# PM3_Bosclone_Shield.net
KiCad netlist of a schematic drawn in Altium Designer
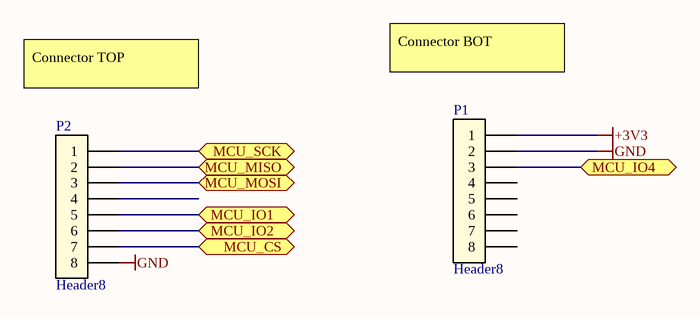
[diagram p0: PM3_Bosclone_Shield.SchDoc]

(export (version "E")
  (design (tool "Eeschema 10.0.6"))
  (components
    (comp (ref "P1")
      (value "Header8")
      (footprint "HEADER_8_40_100THRU SIP")
      (description "Header 8 pin")
      (libsource (lib "mConnector") (part "Header8"))
    )
    (comp (ref "P2")
      (value "Header8")
      (footprint "HEADER_8_40_100THRU SIP")
      (description "Header 8 pin")
      (libsource (lib "mConnector") (part "Header8"))
    )
  )
  (nets
    (net (code "1") (name "+3V3") (class "Default")
      (node (ref "P1") (pin "1") (pinfunction "1_1") (pintype "passive"))
    )
    (net (code "2") (name "/MCU_CS") (class "Default")
      (node (ref "P2") (pin "7") (pinfunction "7_7") (pintype "passive"))
    )
    (net (code "3") (name "/MCU_IO1") (class "Default")
      (node (ref "P2") (pin "5") (pinfunction "5_5") (pintype "passive"))
    )
    (net (code "4") (name "/MCU_IO2") (class "Default")
      (node (ref "P2") (pin "6") (pinfunction "6_6") (pintype "passive"))
    )
    (net (code "5") (name "/MCU_IO4") (class "Default")
      (node (ref "P1") (pin "3") (pinfunction "3_3") (pintype "passive"))
    )
    (net (code "6") (name "/MCU_MISO") (class "Default")
      (node (ref "P2") (pin "2") (pinfunction "2_2") (pintype "passive"))
    )
    (net (code "7") (name "/MCU_MOSI") (class "Default")
      (node (ref "P2") (pin "3") (pinfunction "3_3") (pintype "passive"))
    )
    (net (code "8") (name "/MCU_SCK") (class "Default")
      (node (ref "P2") (pin "1") (pinfunction "1_1") (pintype "passive"))
    )
    (net (code "9") (name "GND") (class "Default")
      (node (ref "P1") (pin "2") (pinfunction "2_2") (pintype "passive"))
      (node (ref "P2") (pin "8") (pinfunction "8_8") (pintype "passive"))
    )
    (net (code "10") (name "unconnected-(P1-Pad4)") (class "Default")
      (node (ref "P1") (pin "4") (pinfunction "4_4") (pintype "passive"))
    )
    (net (code "11") (name "unconnected-(P1-Pad5)") (class "Default")
      (node (ref "P1") (pin "5") (pinfunction "5_5") (pintype "passive"))
    )
    (net (code "12") (name "unconnected-(P1-Pad6)") (class "Default")
      (node (ref "P1") (pin "6") (pinfunction "6_6") (pintype "passive"))
    )
    (net (code "13") (name "unconnected-(P1-Pad7)") (class "Default")
      (node (ref "P1") (pin "7") (pinfunction "7_7") (pintype "passive"))
    )
    (net (code "14") (name "unconnected-(P1-Pad8)") (class "Default")
      (node (ref "P1") (pin "8") (pinfunction "8_8") (pintype "passive"))
    )
    (net (code "15") (name "unconnected-(P2-Pad4)") (class "Default")
      (node (ref "P2") (pin "4") (pinfunction "4_4") (pintype "passive"))
    )
  )
)
